# SevenSegment.net
KiCad netlist of a schematic drawn in EAGLE
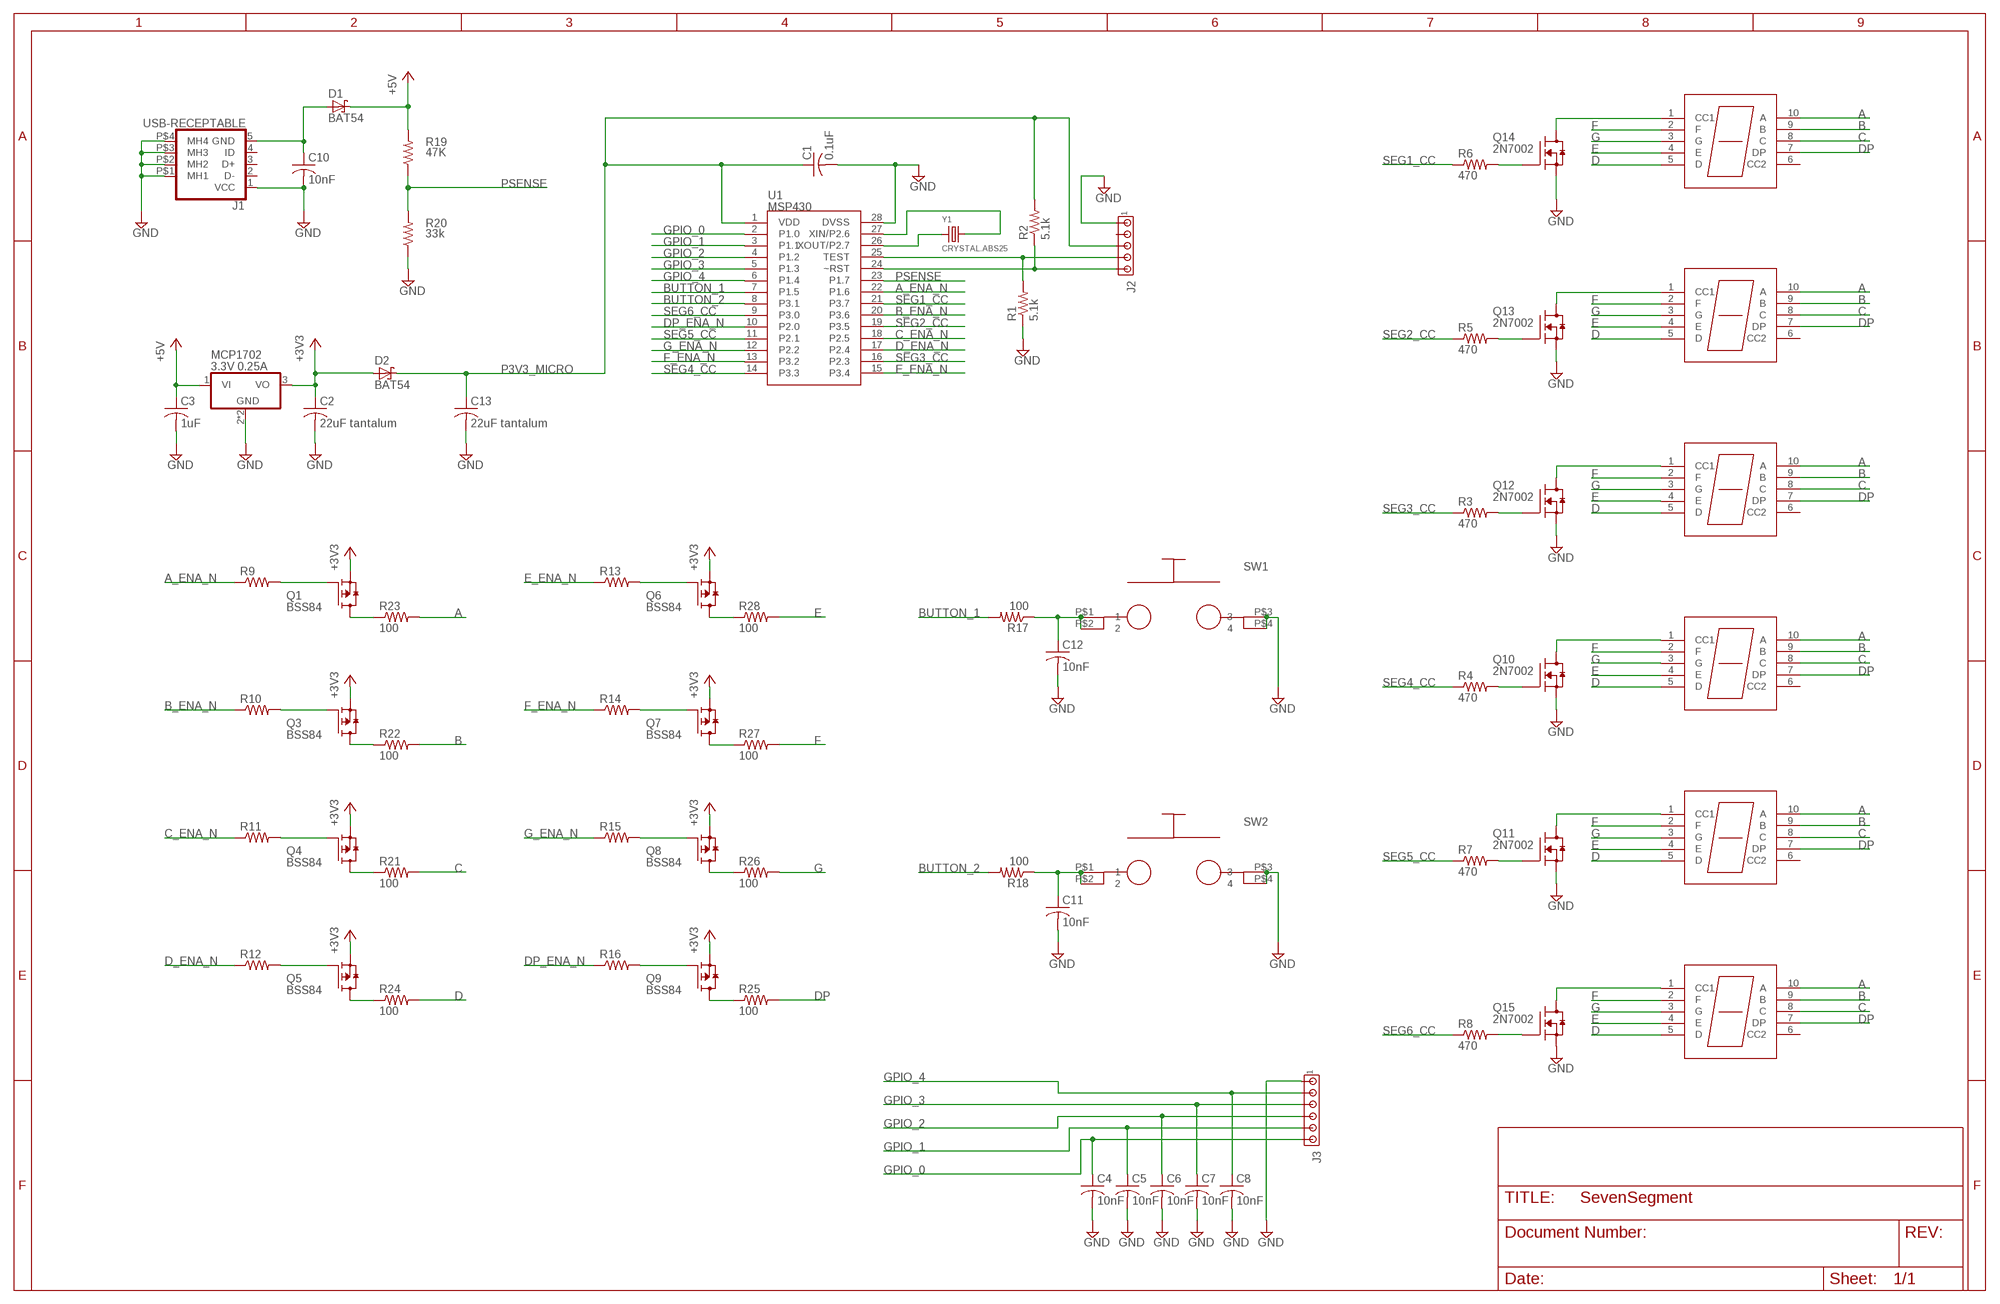
[diagram p0: schematic, sheet 1]

(export (version "E")
  (design (tool "Eeschema 10.0.6"))
  (components
    (comp (ref "C1")
      (value "0.1uF")
      (footprint "eagle-import:C0805")
      (libsource (lib "eagle-import") (part "C-USC0805"))
    )
    (comp (ref "C2")
      (value "22uF tantalum")
      (footprint "eagle-import:C3216")
      (libsource (lib "eagle-import") (part "C-USC3216"))
    )
    (comp (ref "C3")
      (value "1uF")
      (footprint "eagle-import:C0603")
      (libsource (lib "eagle-import") (part "C-USC0603"))
    )
    (comp (ref "C4")
      (value "10nF")
      (footprint "eagle-import:C0603")
      (libsource (lib "eagle-import") (part "C-USC0603"))
    )
    (comp (ref "C5")
      (value "10nF")
      (footprint "eagle-import:C0603")
      (libsource (lib "eagle-import") (part "C-USC0603"))
    )
    (comp (ref "C6")
      (value "10nF")
      (footprint "eagle-import:C0603")
      (libsource (lib "eagle-import") (part "C-USC0603"))
    )
    (comp (ref "C7")
      (value "10nF")
      (footprint "eagle-import:C0603")
      (libsource (lib "eagle-import") (part "C-USC0603"))
    )
    (comp (ref "C8")
      (value "10nF")
      (footprint "eagle-import:C0603")
      (libsource (lib "eagle-import") (part "C-USC0603"))
    )
    (comp (ref "C10")
      (value "10nF")
      (footprint "eagle-import:C0603")
      (libsource (lib "eagle-import") (part "C-USC0603"))
    )
    (comp (ref "C11")
      (value "10nF")
      (footprint "eagle-import:C0603")
      (libsource (lib "eagle-import") (part "C-USC0603"))
    )
    (comp (ref "C12")
      (value "10nF")
      (footprint "eagle-import:C0603")
      (libsource (lib "eagle-import") (part "C-USC0603"))
    )
    (comp (ref "C13")
      (value "22uF tantalum")
      (footprint "eagle-import:C3216")
      (libsource (lib "eagle-import") (part "C-USC3216"))
    )
    (comp (ref "D1")
      (value "BAT54")
      (footprint "eagle-import:SOT23")
      (libsource (lib "eagle-import") (part "BAT54"))
    )
    (comp (ref "D2")
      (value "BAT54")
      (footprint "eagle-import:SOT23")
      (libsource (lib "eagle-import") (part "BAT54"))
    )
    (comp (ref "DP1")
      (value "SEVENSEGMENT")
      (footprint "eagle-import:LA-401")
      (libsource (lib "eagle-import") (part "SEVENSEGMENT"))
    )
    (comp (ref "DP2")
      (value "SEVENSEGMENT")
      (footprint "eagle-import:LA-401")
      (libsource (lib "eagle-import") (part "SEVENSEGMENT"))
    )
    (comp (ref "DP3")
      (value "SEVENSEGMENT")
      (footprint "eagle-import:LA-401")
      (libsource (lib "eagle-import") (part "SEVENSEGMENT"))
    )
    (comp (ref "DP4")
      (value "SEVENSEGMENT")
      (footprint "eagle-import:LA-401")
      (libsource (lib "eagle-import") (part "SEVENSEGMENT"))
    )
    (comp (ref "DP5")
      (value "SEVENSEGMENT")
      (footprint "eagle-import:LA-401")
      (libsource (lib "eagle-import") (part "SEVENSEGMENT"))
    )
    (comp (ref "DP6")
      (value "SEVENSEGMENT")
      (footprint "eagle-import:LA-401")
      (libsource (lib "eagle-import") (part "SEVENSEGMENT"))
    )
    (comp (ref "J1")
      (value "USB-RECEPTABLE")
      (footprint "eagle-import:FCI-10103594-0001LF")
      (libsource (lib "eagle-import") (part "USB-RECEPTABLE"))
    )
    (comp (ref "J2")
      (value "MTA05-100")
      (footprint "eagle-import:10X05MTA")
      (libsource (lib "eagle-import") (part "MTA05-100"))
    )
    (comp (ref "J3")
      (value "MTA06-100")
      (footprint "eagle-import:10X06MTA")
      (libsource (lib "eagle-import") (part "MTA06-100"))
    )
    (comp (ref "Q1")
      (value "BSS84")
      (footprint "eagle-import:SOT-23")
      (libsource (lib "eagle-import") (part "BSS84"))
    )
    (comp (ref "Q3")
      (value "BSS84")
      (footprint "eagle-import:SOT-23")
      (libsource (lib "eagle-import") (part "BSS84"))
    )
    (comp (ref "Q4")
      (value "BSS84")
      (footprint "eagle-import:SOT-23")
      (libsource (lib "eagle-import") (part "BSS84"))
    )
    (comp (ref "Q5")
      (value "BSS84")
      (footprint "eagle-import:SOT-23")
      (libsource (lib "eagle-import") (part "BSS84"))
    )
    (comp (ref "Q6")
      (value "BSS84")
      (footprint "eagle-import:SOT-23")
      (libsource (lib "eagle-import") (part "BSS84"))
    )
    (comp (ref "Q7")
      (value "BSS84")
      (footprint "eagle-import:SOT-23")
      (libsource (lib "eagle-import") (part "BSS84"))
    )
    (comp (ref "Q8")
      (value "BSS84")
      (footprint "eagle-import:SOT-23")
      (libsource (lib "eagle-import") (part "BSS84"))
    )
    (comp (ref "Q9")
      (value "BSS84")
      (footprint "eagle-import:SOT-23")
      (libsource (lib "eagle-import") (part "BSS84"))
    )
    (comp (ref "Q10")
      (value "2N7002")
      (footprint "eagle-import:SOT-23")
      (libsource (lib "eagle-import") (part "2N7002"))
    )
    (comp (ref "Q11")
      (value "2N7002")
      (footprint "eagle-import:SOT-23")
      (libsource (lib "eagle-import") (part "2N7002"))
    )
    (comp (ref "Q12")
      (value "2N7002")
      (footprint "eagle-import:SOT-23")
      (libsource (lib "eagle-import") (part "2N7002"))
    )
    (comp (ref "Q13")
      (value "2N7002")
      (footprint "eagle-import:SOT-23")
      (libsource (lib "eagle-import") (part "2N7002"))
    )
    (comp (ref "Q14")
      (value "2N7002")
      (footprint "eagle-import:SOT-23")
      (libsource (lib "eagle-import") (part "2N7002"))
    )
    (comp (ref "Q15")
      (value "2N7002")
      (footprint "eagle-import:SOT-23")
      (libsource (lib "eagle-import") (part "2N7002"))
    )
    (comp (ref "R1")
      (value "5.1k")
      (footprint "eagle-import:R0603")
      (libsource (lib "eagle-import") (part "R-US_R0603"))
    )
    (comp (ref "R2")
      (value "5.1k")
      (footprint "eagle-import:R0603")
      (libsource (lib "eagle-import") (part "R-US_R0603"))
    )
    (comp (ref "R3")
      (value "470")
      (footprint "eagle-import:R0603")
      (libsource (lib "eagle-import") (part "R-US_R0603"))
    )
    (comp (ref "R4")
      (value "470")
      (footprint "eagle-import:R0603")
      (libsource (lib "eagle-import") (part "R-US_R0603"))
    )
    (comp (ref "R5")
      (value "470")
      (footprint "eagle-import:R0603")
      (libsource (lib "eagle-import") (part "R-US_R0603"))
    )
    (comp (ref "R6")
      (value "470")
      (footprint "eagle-import:R0603")
      (libsource (lib "eagle-import") (part "R-US_R0603"))
    )
    (comp (ref "R7")
      (value "470")
      (footprint "eagle-import:R0603")
      (libsource (lib "eagle-import") (part "R-US_R0603"))
    )
    (comp (ref "R8")
      (value "470")
      (footprint "eagle-import:R0603")
      (libsource (lib "eagle-import") (part "R-US_R0603"))
    )
    (comp (ref "R9")
      (value "R-US_R0603")
      (footprint "eagle-import:R0603")
      (libsource (lib "eagle-import") (part "R-US_R0603"))
    )
    (comp (ref "R10")
      (value "R-US_R0603")
      (footprint "eagle-import:R0603")
      (libsource (lib "eagle-import") (part "R-US_R0603"))
    )
    (comp (ref "R11")
      (value "R-US_R0603")
      (footprint "eagle-import:R0603")
      (libsource (lib "eagle-import") (part "R-US_R0603"))
    )
    (comp (ref "R12")
      (value "R-US_R0603")
      (footprint "eagle-import:R0603")
      (libsource (lib "eagle-import") (part "R-US_R0603"))
    )
    (comp (ref "R13")
      (value "R-US_R0603")
      (footprint "eagle-import:R0603")
      (libsource (lib "eagle-import") (part "R-US_R0603"))
    )
    (comp (ref "R14")
      (value "R-US_R0603")
      (footprint "eagle-import:R0603")
      (libsource (lib "eagle-import") (part "R-US_R0603"))
    )
    (comp (ref "R15")
      (value "R-US_R0603")
      (footprint "eagle-import:R0603")
      (libsource (lib "eagle-import") (part "R-US_R0603"))
    )
    (comp (ref "R16")
      (value "R-US_R0603")
      (footprint "eagle-import:R0603")
      (libsource (lib "eagle-import") (part "R-US_R0603"))
    )
    (comp (ref "R17")
      (value "100")
      (footprint "eagle-import:R0603")
      (libsource (lib "eagle-import") (part "R-US_R0603"))
    )
    (comp (ref "R18")
      (value "100")
      (footprint "eagle-import:R0603")
      (libsource (lib "eagle-import") (part "R-US_R0603"))
    )
    (comp (ref "R19")
      (value "47K")
      (footprint "eagle-import:R0603")
      (libsource (lib "eagle-import") (part "R-US_R0603"))
    )
    (comp (ref "R20")
      (value "33k")
      (footprint "eagle-import:R0603")
      (libsource (lib "eagle-import") (part "R-US_R0603"))
    )
    (comp (ref "R21")
      (value "100")
      (footprint "eagle-import:R0603")
      (libsource (lib "eagle-import") (part "R-US_R0603"))
    )
    (comp (ref "R22")
      (value "100")
      (footprint "eagle-import:R0603")
      (libsource (lib "eagle-import") (part "R-US_R0603"))
    )
    (comp (ref "R23")
      (value "100")
      (footprint "eagle-import:R0603")
      (libsource (lib "eagle-import") (part "R-US_R0603"))
    )
    (comp (ref "R24")
      (value "100")
      (footprint "eagle-import:R0603")
      (libsource (lib "eagle-import") (part "R-US_R0603"))
    )
    (comp (ref "R25")
      (value "100")
      (footprint "eagle-import:R0603")
      (libsource (lib "eagle-import") (part "R-US_R0603"))
    )
    (comp (ref "R26")
      (value "100")
      (footprint "eagle-import:R0603")
      (libsource (lib "eagle-import") (part "R-US_R0603"))
    )
    (comp (ref "R27")
      (value "100")
      (footprint "eagle-import:R0603")
      (libsource (lib "eagle-import") (part "R-US_R0603"))
    )
    (comp (ref "R28")
      (value "100")
      (footprint "eagle-import:R0603")
      (libsource (lib "eagle-import") (part "R-US_R0603"))
    )
    (comp (ref "SW1")
      (value "BUTTON")
      (footprint "eagle-import:TL6100CF300QP")
      (libsource (lib "eagle-import") (part "BUTTON"))
    )
    (comp (ref "SW2")
      (value "BUTTON")
      (footprint "eagle-import:TL6100CF300QP")
      (libsource (lib "eagle-import") (part "BUTTON"))
    )
    (comp (ref "U1")
      (value "MSP430")
      (footprint "eagle-import:TSSOP28")
      (libsource (lib "eagle-import") (part "MICRO"))
    )
    (comp (ref "U12")
      (value "VOLTAGEREG")
      (footprint "eagle-import:SOT223")
      (libsource (lib "eagle-import") (part "VOLTAGEREG"))
    )
    (comp (ref "Y1")
      (value "CRYSTAL.ABS25")
      (footprint "eagle-import:ABS25")
      (libsource (lib "eagle-import") (part "CRYSTAL.ABS25"))
    )
  )
  (nets
    (net (code "1") (name "+3V3") (class "Default")
      (node (ref "C2") (pin "1") (pinfunction "1_1") (pintype "passive"))
      (node (ref "D2") (pin "1") (pinfunction "A_1") (pintype "passive"))
      (node (ref "Q1") (pin "2") (pinfunction "S_2") (pintype "passive"))
      (node (ref "Q3") (pin "2") (pinfunction "S_2") (pintype "passive"))
      (node (ref "Q4") (pin "2") (pinfunction "S_2") (pintype "passive"))
      (node (ref "Q5") (pin "2") (pinfunction "S_2") (pintype "passive"))
      (node (ref "Q6") (pin "2") (pinfunction "S_2") (pintype "passive"))
      (node (ref "Q7") (pin "2") (pinfunction "S_2") (pintype "passive"))
      (node (ref "Q8") (pin "2") (pinfunction "S_2") (pintype "passive"))
      (node (ref "Q9") (pin "2") (pinfunction "S_2") (pintype "passive"))
      (node (ref "U12") (pin "3") (pinfunction "VO_3") (pintype "passive"))
    )
    (net (code "2") (name "+5V") (class "Default")
      (node (ref "C3") (pin "1") (pinfunction "1_1") (pintype "passive"))
      (node (ref "D1") (pin "3") (pinfunction "C_3") (pintype "passive"))
      (node (ref "R19") (pin "2") (pinfunction "2_2") (pintype "passive"))
      (node (ref "U12") (pin "1") (pinfunction "VI_1") (pintype "input"))
    )
    (net (code "3") (name "/A") (class "Default")
      (node (ref "DP1") (pin "10") (pinfunction "A_10") (pintype "passive"))
      (node (ref "DP2") (pin "10") (pinfunction "A_10") (pintype "passive"))
      (node (ref "DP3") (pin "10") (pinfunction "A_10") (pintype "passive"))
      (node (ref "DP4") (pin "10") (pinfunction "A_10") (pintype "passive"))
      (node (ref "DP5") (pin "10") (pinfunction "A_10") (pintype "passive"))
      (node (ref "DP6") (pin "10") (pinfunction "A_10") (pintype "passive"))
      (node (ref "R23") (pin "2") (pinfunction "2_2") (pintype "passive"))
    )
    (net (code "4") (name "/A_ENA_N") (class "Default")
      (node (ref "R9") (pin "1") (pinfunction "1_1") (pintype "passive"))
      (node (ref "U1") (pin "22") (pinfunction "P1.6_22") (pintype "bidirectional"))
    )
    (net (code "5") (name "/B") (class "Default")
      (node (ref "DP1") (pin "9") (pinfunction "B_9") (pintype "passive"))
      (node (ref "DP2") (pin "9") (pinfunction "B_9") (pintype "passive"))
      (node (ref "DP3") (pin "9") (pinfunction "B_9") (pintype "passive"))
      (node (ref "DP4") (pin "9") (pinfunction "B_9") (pintype "passive"))
      (node (ref "DP5") (pin "9") (pinfunction "B_9") (pintype "passive"))
      (node (ref "DP6") (pin "9") (pinfunction "B_9") (pintype "passive"))
      (node (ref "R22") (pin "2") (pinfunction "2_2") (pintype "passive"))
    )
    (net (code "6") (name "/BUTTON_1") (class "Default")
      (node (ref "R17") (pin "2") (pinfunction "2_2") (pintype "passive"))
      (node (ref "U1") (pin "7") (pinfunction "P1.5_7") (pintype "bidirectional"))
    )
    (net (code "7") (name "/BUTTON_2") (class "Default")
      (node (ref "R18") (pin "2") (pinfunction "2_2") (pintype "passive"))
      (node (ref "U1") (pin "8") (pinfunction "P3.1_8") (pintype "bidirectional"))
    )
    (net (code "8") (name "/B_ENA_N") (class "Default")
      (node (ref "R10") (pin "1") (pinfunction "1_1") (pintype "passive"))
      (node (ref "U1") (pin "20") (pinfunction "P3.6_20") (pintype "bidirectional"))
    )
    (net (code "9") (name "/C") (class "Default")
      (node (ref "DP1") (pin "8") (pinfunction "C_8") (pintype "passive"))
      (node (ref "DP2") (pin "8") (pinfunction "C_8") (pintype "passive"))
      (node (ref "DP3") (pin "8") (pinfunction "C_8") (pintype "passive"))
      (node (ref "DP4") (pin "8") (pinfunction "C_8") (pintype "passive"))
      (node (ref "DP5") (pin "8") (pinfunction "C_8") (pintype "passive"))
      (node (ref "DP6") (pin "8") (pinfunction "C_8") (pintype "passive"))
      (node (ref "R21") (pin "2") (pinfunction "2_2") (pintype "passive"))
    )
    (net (code "10") (name "/C_ENA_N") (class "Default")
      (node (ref "R11") (pin "1") (pinfunction "1_1") (pintype "passive"))
      (node (ref "U1") (pin "18") (pinfunction "P2.5_18") (pintype "bidirectional"))
    )
    (net (code "11") (name "/D") (class "Default")
      (node (ref "DP1") (pin "5") (pinfunction "D_5") (pintype "passive"))
      (node (ref "DP2") (pin "5") (pinfunction "D_5") (pintype "passive"))
      (node (ref "DP3") (pin "5") (pinfunction "D_5") (pintype "passive"))
      (node (ref "DP4") (pin "5") (pinfunction "D_5") (pintype "passive"))
      (node (ref "DP5") (pin "5") (pinfunction "D_5") (pintype "passive"))
      (node (ref "DP6") (pin "5") (pinfunction "D_5") (pintype "passive"))
      (node (ref "R24") (pin "2") (pinfunction "2_2") (pintype "passive"))
    )
    (net (code "12") (name "/DP") (class "Default")
      (node (ref "DP1") (pin "7") (pinfunction "DP_7") (pintype "passive"))
      (node (ref "DP2") (pin "7") (pinfunction "DP_7") (pintype "passive"))
      (node (ref "DP3") (pin "7") (pinfunction "DP_7") (pintype "passive"))
      (node (ref "DP4") (pin "7") (pinfunction "DP_7") (pintype "passive"))
      (node (ref "DP5") (pin "7") (pinfunction "DP_7") (pintype "passive"))
      (node (ref "DP6") (pin "7") (pinfunction "DP_7") (pintype "passive"))
      (node (ref "R25") (pin "2") (pinfunction "2_2") (pintype "passive"))
    )
    (net (code "13") (name "/DP_ENA_N") (class "Default")
      (node (ref "R16") (pin "1") (pinfunction "1_1") (pintype "passive"))
      (node (ref "U1") (pin "10") (pinfunction "P2.0_10") (pintype "bidirectional"))
    )
    (net (code "14") (name "/D_ENA_N") (class "Default")
      (node (ref "R12") (pin "1") (pinfunction "1_1") (pintype "passive"))
      (node (ref "U1") (pin "17") (pinfunction "P2.4_17") (pintype "bidirectional"))
    )
    (net (code "15") (name "/E") (class "Default")
      (node (ref "DP1") (pin "4") (pinfunction "E_4") (pintype "passive"))
      (node (ref "DP2") (pin "4") (pinfunction "E_4") (pintype "passive"))
      (node (ref "DP3") (pin "4") (pinfunction "E_4") (pintype "passive"))
      (node (ref "DP4") (pin "4") (pinfunction "E_4") (pintype "passive"))
      (node (ref "DP5") (pin "4") (pinfunction "E_4") (pintype "passive"))
      (node (ref "DP6") (pin "4") (pinfunction "E_4") (pintype "passive"))
      (node (ref "R28") (pin "2") (pinfunction "2_2") (pintype "passive"))
    )
    (net (code "16") (name "/E_ENA_N") (class "Default")
      (node (ref "R13") (pin "1") (pinfunction "1_1") (pintype "passive"))
      (node (ref "U1") (pin "15") (pinfunction "P3.4_15") (pintype "bidirectional"))
    )
    (net (code "17") (name "/F") (class "Default")
      (node (ref "DP1") (pin "2") (pinfunction "F_2") (pintype "passive"))
      (node (ref "DP2") (pin "2") (pinfunction "F_2") (pintype "passive"))
      (node (ref "DP3") (pin "2") (pinfunction "F_2") (pintype "passive"))
      (node (ref "DP4") (pin "2") (pinfunction "F_2") (pintype "passive"))
      (node (ref "DP5") (pin "2") (pinfunction "F_2") (pintype "passive"))
      (node (ref "DP6") (pin "2") (pinfunction "F_2") (pintype "passive"))
      (node (ref "R27") (pin "2") (pinfunction "2_2") (pintype "passive"))
    )
    (net (code "18") (name "/F_ENA_N") (class "Default")
      (node (ref "R14") (pin "1") (pinfunction "1_1") (pintype "passive"))
      (node (ref "U1") (pin "13") (pinfunction "P3.2_13") (pintype "bidirectional"))
    )
    (net (code "19") (name "/G") (class "Default")
      (node (ref "DP1") (pin "3") (pinfunction "G_3") (pintype "passive"))
      (node (ref "DP2") (pin "3") (pinfunction "G_3") (pintype "passive"))
      (node (ref "DP3") (pin "3") (pinfunction "G_3") (pintype "passive"))
      (node (ref "DP4") (pin "3") (pinfunction "G_3") (pintype "passive"))
      (node (ref "DP5") (pin "3") (pinfunction "G_3") (pintype "passive"))
      (node (ref "DP6") (pin "3") (pinfunction "G_3") (pintype "passive"))
      (node (ref "R26") (pin "2") (pinfunction "2_2") (pintype "passive"))
    )
    (net (code "20") (name "/GPIO_0") (class "Default")
      (node (ref "C4") (pin "1") (pinfunction "1_1") (pintype "passive"))
      (node (ref "J3") (pin "6") (pinfunction "6_6") (pintype "passive"))
      (node (ref "U1") (pin "2") (pinfunction "P1.0_2") (pintype "bidirectional"))
    )
    (net (code "21") (name "/GPIO_1") (class "Default")
      (node (ref "C5") (pin "1") (pinfunction "1_1") (pintype "passive"))
      (node (ref "J3") (pin "5") (pinfunction "5_5") (pintype "passive"))
      (node (ref "U1") (pin "3") (pinfunction "P1.1_3") (pintype "bidirectional"))
    )
    (net (code "22") (name "/GPIO_2") (class "Default")
      (node (ref "C6") (pin "1") (pinfunction "1_1") (pintype "passive"))
      (node (ref "J3") (pin "4") (pinfunction "4_4") (pintype "passive"))
      (node (ref "U1") (pin "4") (pinfunction "P1.2_4") (pintype "bidirectional"))
    )
    (net (code "23") (name "/GPIO_3") (class "Default")
      (node (ref "C7") (pin "1") (pinfunction "1_1") (pintype "passive"))
      (node (ref "J3") (pin "3") (pinfunction "3_3") (pintype "passive"))
      (node (ref "U1") (pin "5") (pinfunction "P1.3_5") (pintype "bidirectional"))
    )
    (net (code "24") (name "/GPIO_4") (class "Default")
      (node (ref "C8") (pin "1") (pinfunction "1_1") (pintype "passive"))
      (node (ref "J3") (pin "2") (pinfunction "2_2") (pintype "passive"))
      (node (ref "U1") (pin "6") (pinfunction "P1.4_6") (pintype "bidirectional"))
    )
    (net (code "25") (name "/G_ENA_N") (class "Default")
      (node (ref "R15") (pin "1") (pinfunction "1_1") (pintype "passive"))
      (node (ref "U1") (pin "12") (pinfunction "P2.2_12") (pintype "bidirectional"))
    )
    (net (code "26") (name "/P3V3_MICRO") (class "Default")
      (node (ref "C1") (pin "1") (pinfunction "1_1") (pintype "passive"))
      (node (ref "C13") (pin "1") (pinfunction "1_1") (pintype "passive"))
      (node (ref "D2") (pin "3") (pinfunction "C_3") (pintype "passive"))
      (node (ref "J2") (pin "3") (pinfunction "3_3") (pintype "passive"))
      (node (ref "R2") (pin "2") (pinfunction "2_2") (pintype "passive"))
      (node (ref "U1") (pin "1") (pinfunction "VDD_1") (pintype "power_in"))
    )
    (net (code "27") (name "/PSENSE") (class "Default")
      (node (ref "R19") (pin "1") (pinfunction "1_1") (pintype "passive"))
      (node (ref "R20") (pin "2") (pinfunction "2_2") (pintype "passive"))
      (node (ref "U1") (pin "23") (pinfunction "P1.7_23") (pintype "bidirectional"))
    )
    (net (code "28") (name "/SEG1_CC") (class "Default")
      (node (ref "R6") (pin "1") (pinfunction "1_1") (pintype "passive"))
      (node (ref "U1") (pin "21") (pinfunction "P3.7_21") (pintype "bidirectional"))
    )
    (net (code "29") (name "/SEG2_CC") (class "Default")
      (node (ref "R5") (pin "1") (pinfunction "1_1") (pintype "passive"))
      (node (ref "U1") (pin "19") (pinfunction "P3.5_19") (pintype "bidirectional"))
    )
    (net (code "30") (name "/SEG3_CC") (class "Default")
      (node (ref "R3") (pin "1") (pinfunction "1_1") (pintype "passive"))
      (node (ref "U1") (pin "16") (pinfunction "P2.3_16") (pintype "bidirectional"))
    )
    (net (code "31") (name "/SEG4_CC") (class "Default")
      (node (ref "R4") (pin "1") (pinfunction "1_1") (pintype "passive"))
      (node (ref "U1") (pin "14") (pinfunction "P3.3_14") (pintype "bidirectional"))
    )
    (net (code "32") (name "/SEG5_CC") (class "Default")
      (node (ref "R7") (pin "1") (pinfunction "1_1") (pintype "passive"))
      (node (ref "U1") (pin "11") (pinfunction "P2.1_11") (pintype "bidirectional"))
    )
    (net (code "33") (name "/SEG6_CC") (class "Default")
      (node (ref "R8") (pin "1") (pinfunction "1_1") (pintype "passive"))
      (node (ref "U1") (pin "9") (pinfunction "P3.0_9") (pintype "bidirectional"))
    )
    (net (code "34") (name "GND") (class "Default")
      (node (ref "C1") (pin "2") (pinfunction "2_2") (pintype "passive"))
      (node (ref "C10") (pin "2") (pinfunction "2_2") (pintype "passive"))
      (node (ref "C11") (pin "2") (pinfunction "2_2") (pintype "passive"))
      (node (ref "C12") (pin "2") (pinfunction "2_2") (pintype "passive"))
      (node (ref "C13") (pin "2") (pinfunction "2_2") (pintype "passive"))
      (node (ref "C2") (pin "2") (pinfunction "2_2") (pintype "passive"))
      (node (ref "C3") (pin "2") (pinfunction "2_2") (pintype "passive"))
      (node (ref "C4") (pin "2") (pinfunction "2_2") (pintype "passive"))
      (node (ref "C5") (pin "2") (pinfunction "2_2") (pintype "passive"))
      (node (ref "C6") (pin "2") (pinfunction "2_2") (pintype "passive"))
      (node (ref "C7") (pin "2") (pinfunction "2_2") (pintype "passive"))
      (node (ref "C8") (pin "2") (pinfunction "2_2") (pintype "passive"))
      (node (ref "J1") (pin "1") (pinfunction "VCC_1") (pintype "bidirectional"))
      (node (ref "J1") (pin "P$1") (pinfunction "MH1_P$1") (pintype "bidirectional"))
      (node (ref "J1") (pin "P$2") (pinfunction "MH2_P$2") (pintype "bidirectional"))
      (node (ref "J1") (pin "P$3") (pinfunction "MH3_P$3") (pintype "bidirectional"))
      (node (ref "J1") (pin "P$4") (pinfunction "MH4_P$4") (pintype "bidirectional"))
      (node (ref "J2") (pin "1") (pinfunction "1_1") (pintype "passive"))
      (node (ref "J3") (pin "1") (pinfunction "1_1") (pintype "passive"))
      (node (ref "Q10") (pin "2") (pinfunction "S_2") (pintype "passive"))
      (node (ref "Q11") (pin "2") (pinfunction "S_2") (pintype "passive"))
      (node (ref "Q12") (pin "2") (pinfunction "S_2") (pintype "passive"))
      (node (ref "Q13") (pin "2") (pinfunction "S_2") (pintype "passive"))
      (node (ref "Q14") (pin "2") (pinfunction "S_2") (pintype "passive"))
      (node (ref "Q15") (pin "2") (pinfunction "S_2") (pintype "passive"))
      (node (ref "R1") (pin "1") (pinfunction "1_1") (pintype "passive"))
      (node (ref "R20") (pin "1") (pinfunction "1_1") (pintype "passive"))
      (node (ref "SW1") (pin "P$3") (pinfunction "3_P$3") (pintype "passive"))
      (node (ref "SW1") (pin "P$4") (pinfunction "4_P$4") (pintype "passive"))
      (node (ref "SW2") (pin "P$3") (pinfunction "3_P$3") (pintype "passive"))
      (node (ref "SW2") (pin "P$4") (pinfunction "4_P$4") (pintype "passive"))
      (node (ref "U1") (pin "28") (pinfunction "DVSS_28") (pintype "power_in"))
      (node (ref "U12") (pin "2") (pinfunction "GND_2") (pintype "passive"))
      (node (ref "U12") (pin "4") (pinfunction "GND_4") (pintype "passive"))
    )
    (net (code "35") (name "Net-(D1-A)") (class "Default")
      (node (ref "C10") (pin "1") (pinfunction "1_1") (pintype "passive"))
      (node (ref "D1") (pin "1") (pinfunction "A_1") (pintype "passive"))
      (node (ref "J1") (pin "5") (pinfunction "GND_5") (pintype "bidirectional"))
    )
    (net (code "36") (name "Net-(DP1-CC1)") (class "Default")
      (node (ref "DP1") (pin "1") (pinfunction "CC1_1") (pintype "passive"))
      (node (ref "Q14") (pin "3") (pinfunction "D_3") (pintype "passive"))
    )
    (net (code "37") (name "Net-(DP2-CC1)") (class "Default")
      (node (ref "DP2") (pin "1") (pinfunction "CC1_1") (pintype "passive"))
      (node (ref "Q13") (pin "3") (pinfunction "D_3") (pintype "passive"))
    )
    (net (code "38") (name "Net-(DP3-CC1)") (class "Default")
      (node (ref "DP3") (pin "1") (pinfunction "CC1_1") (pintype "passive"))
      (node (ref "Q12") (pin "3") (pinfunction "D_3") (pintype "passive"))
    )
    (net (code "39") (name "Net-(DP4-CC1)") (class "Default")
      (node (ref "DP4") (pin "1") (pinfunction "CC1_1") (pintype "passive"))
      (node (ref "Q10") (pin "3") (pinfunction "D_3") (pintype "passive"))
    )
    (net (code "40") (name "Net-(DP5-CC1)") (class "Default")
      (node (ref "DP5") (pin "1") (pinfunction "CC1_1") (pintype "passive"))
      (node (ref "Q11") (pin "3") (pinfunction "D_3") (pintype "passive"))
    )
    (net (code "41") (name "Net-(DP6-CC1)") (class "Default")
      (node (ref "DP6") (pin "1") (pinfunction "CC1_1") (pintype "passive"))
      (node (ref "Q15") (pin "3") (pinfunction "D_3") (pintype "passive"))
    )
    (net (code "42") (name "Net-(Q1-D)") (class "Default")
      (node (ref "Q1") (pin "3") (pinfunction "D_3") (pintype "passive"))
      (node (ref "R23") (pin "1") (pinfunction "1_1") (pintype "passive"))
    )
    (net (code "43") (name "Net-(Q1-G)") (class "Default")
      (node (ref "Q1") (pin "1") (pinfunction "G_1") (pintype "passive"))
      (node (ref "R9") (pin "2") (pinfunction "2_2") (pintype "passive"))
    )
    (net (code "44") (name "Net-(Q3-D)") (class "Default")
      (node (ref "Q3") (pin "3") (pinfunction "D_3") (pintype "passive"))
      (node (ref "R22") (pin "1") (pinfunction "1_1") (pintype "passive"))
    )
    (net (code "45") (name "Net-(Q3-G)") (class "Default")
      (node (ref "Q3") (pin "1") (pinfunction "G_1") (pintype "passive"))
      (node (ref "R10") (pin "2") (pinfunction "2_2") (pintype "passive"))
    )
    (net (code "46") (name "Net-(Q4-D)") (class "Default")
      (node (ref "Q4") (pin "3") (pinfunction "D_3") (pintype "passive"))
      (node (ref "R21") (pin "1") (pinfunction "1_1") (pintype "passive"))
    )
    (net (code "47") (name "Net-(Q4-G)") (class "Default")
      (node (ref "Q4") (pin "1") (pinfunction "G_1") (pintype "passive"))
      (node (ref "R11") (pin "2") (pinfunction "2_2") (pintype "passive"))
    )
    (net (code "48") (name "Net-(Q5-D)") (class "Default")
      (node (ref "Q5") (pin "3") (pinfunction "D_3") (pintype "passive"))
      (node (ref "R24") (pin "1") (pinfunction "1_1") (pintype "passive"))
    )
    (net (code "49") (name "Net-(Q5-G)") (class "Default")
      (node (ref "Q5") (pin "1") (pinfunction "G_1") (pintype "passive"))
      (node (ref "R12") (pin "2") (pinfunction "2_2") (pintype "passive"))
    )
    (net (code "50") (name "Net-(Q6-D)") (class "Default")
      (node (ref "Q6") (pin "3") (pinfunction "D_3") (pintype "passive"))
      (node (ref "R28") (pin "1") (pinfunction "1_1") (pintype "passive"))
    )
    (net (code "51") (name "Net-(Q6-G)") (class "Default")
      (node (ref "Q6") (pin "1") (pinfunction "G_1") (pintype "passive"))
      (node (ref "R13") (pin "2") (pinfunction "2_2") (pintype "passive"))
    )
    (net (code "52") (name "Net-(Q7-D)") (class "Default")
      (node (ref "Q7") (pin "3") (pinfunction "D_3") (pintype "passive"))
      (node (ref "R27") (pin "1") (pinfunction "1_1") (pintype "passive"))
    )
    (net (code "53") (name "Net-(Q7-G)") (class "Default")
      (node (ref "Q7") (pin "1") (pinfunction "G_1") (pintype "passive"))
      (node (ref "R14") (pin "2") (pinfunction "2_2") (pintype "passive"))
    )
    (net (code "54") (name "Net-(Q8-D)") (class "Default")
      (node (ref "Q8") (pin "3") (pinfunction "D_3") (pintype "passive"))
      (node (ref "R26") (pin "1") (pinfunction "1_1") (pintype "passive"))
    )
    (net (code "55") (name "Net-(Q8-G)") (class "Default")
      (node (ref "Q8") (pin "1") (pinfunction "G_1") (pintype "passive"))
      (node (ref "R15") (pin "2") (pinfunction "2_2") (pintype "passive"))
    )
    (net (code "56") (name "Net-(Q9-D)") (class "Default")
      (node (ref "Q9") (pin "3") (pinfunction "D_3") (pintype "passive"))
      (node (ref "R25") (pin "1") (pinfunction "1_1") (pintype "passive"))
    )
    (net (code "57") (name "Net-(Q9-G)") (class "Default")
      (node (ref "Q9") (pin "1") (pinfunction "G_1") (pintype "passive"))
      (node (ref "R16") (pin "2") (pinfunction "2_2") (pintype "passive"))
    )
    (net (code "58") (name "Net-(Q10-G)") (class "Default")
      (node (ref "Q10") (pin "1") (pinfunction "G_1") (pintype "passive"))
      (node (ref "R4") (pin "2") (pinfunction "2_2") (pintype "passive"))
    )
    (net (code "59") (name "Net-(Q11-G)") (class "Default")
      (node (ref "Q11") (pin "1") (pinfunction "G_1") (pintype "passive"))
      (node (ref "R7") (pin "2") (pinfunction "2_2") (pintype "passive"))
    )
    (net (code "60") (name "Net-(Q12-G)") (class "Default")
      (node (ref "Q12") (pin "1") (pinfunction "G_1") (pintype "passive"))
      (node (ref "R3") (pin "2") (pinfunction "2_2") (pintype "passive"))
    )
    (net (code "61") (name "Net-(Q13-G)") (class "Default")
      (node (ref "Q13") (pin "1") (pinfunction "G_1") (pintype "passive"))
      (node (ref "R5") (pin "2") (pinfunction "2_2") (pintype "passive"))
    )
    (net (code "62") (name "Net-(Q14-G)") (class "Default")
      (node (ref "Q14") (pin "1") (pinfunction "G_1") (pintype "passive"))
      (node (ref "R6") (pin "2") (pinfunction "2_2") (pintype "passive"))
    )
    (net (code "63") (name "Net-(Q15-G)") (class "Default")
      (node (ref "Q15") (pin "1") (pinfunction "G_1") (pintype "passive"))
      (node (ref "R8") (pin "2") (pinfunction "2_2") (pintype "passive"))
    )
    (net (code "64") (name "Net-(SW1-1)") (class "Default")
      (node (ref "C12") (pin "1") (pinfunction "1_1") (pintype "passive"))
      (node (ref "R17") (pin "1") (pinfunction "1_1") (pintype "passive"))
      (node (ref "SW1") (pin "P$1") (pinfunction "1_P$1") (pintype "passive"))
      (node (ref "SW1") (pin "P$2") (pinfunction "2_P$2") (pintype "passive"))
    )
    (net (code "65") (name "Net-(SW2-1)") (class "Default")
      (node (ref "C11") (pin "1") (pinfunction "1_1") (pintype "passive"))
      (node (ref "R18") (pin "1") (pinfunction "1_1") (pintype "passive"))
      (node (ref "SW2") (pin "P$1") (pinfunction "1_P$1") (pintype "passive"))
      (node (ref "SW2") (pin "P$2") (pinfunction "2_P$2") (pintype "passive"))
    )
    (net (code "66") (name "Net-(U1-TEST)") (class "Default")
      (node (ref "J2") (pin "4") (pinfunction "4_4") (pintype "passive"))
      (node (ref "R1") (pin "2") (pinfunction "2_2") (pintype "passive"))
      (node (ref "U1") (pin "25") (pinfunction "TEST_25") (pintype "bidirectional"))
    )
    (net (code "67") (name "Net-(U1-XIN{slash}P2.6)") (class "Default")
      (node (ref "U1") (pin "27") (pinfunction "XIN/P2.6_27") (pintype "bidirectional"))
      (node (ref "Y1") (pin "4") (pinfunction "2_4") (pintype "passive"))
    )
    (net (code "68") (name "Net-(U1-XOUT{slash}P2.7)") (class "Default")
      (node (ref "U1") (pin "26") (pinfunction "XOUT/P2.7_26") (pintype "bidirectional"))
      (node (ref "Y1") (pin "1") (pinfunction "1_1") (pintype "passive"))
    )
    (net (code "69") (name "Net-(U1-~{RST})") (class "Default")
      (node (ref "J2") (pin "5") (pinfunction "5_5") (pintype "passive"))
      (node (ref "R2") (pin "1") (pinfunction "1_1") (pintype "passive"))
      (node (ref "U1") (pin "24") (pinfunction "~{RST}_24") (pintype "bidirectional"))
    )
    (net (code "70") (name "unconnected-(DP1-CC2-Pad6)") (class "Default")
      (node (ref "DP1") (pin "6") (pinfunction "CC2_6") (pintype "passive"))
    )
    (net (code "71") (name "unconnected-(DP2-CC2-Pad6)") (class "Default")
      (node (ref "DP2") (pin "6") (pinfunction "CC2_6") (pintype "passive"))
    )
    (net (code "72") (name "unconnected-(DP3-CC2-Pad6)") (class "Default")
      (node (ref "DP3") (pin "6") (pinfunction "CC2_6") (pintype "passive"))
    )
    (net (code "73") (name "unconnected-(DP4-CC2-Pad6)") (class "Default")
      (node (ref "DP4") (pin "6") (pinfunction "CC2_6") (pintype "passive"))
    )
    (net (code "74") (name "unconnected-(DP5-CC2-Pad6)") (class "Default")
      (node (ref "DP5") (pin "6") (pinfunction "CC2_6") (pintype "passive"))
    )
    (net (code "75") (name "unconnected-(DP6-CC2-Pad6)") (class "Default")
      (node (ref "DP6") (pin "6") (pinfunction "CC2_6") (pintype "passive"))
    )
    (net (code "76") (name "unconnected-(J1-D+-Pad3)") (class "Default")
      (node (ref "J1") (pin "3") (pinfunction "D+_3") (pintype "bidirectional"))
    )
    (net (code "77") (name "unconnected-(J1-D--Pad2)") (class "Default")
      (node (ref "J1") (pin "2") (pinfunction "D-_2") (pintype "bidirectional"))
    )
    (net (code "78") (name "unconnected-(J1-ID-Pad4)") (class "Default")
      (node (ref "J1") (pin "4") (pinfunction "ID_4") (pintype "bidirectional"))
    )
    (net (code "79") (name "unconnected-(J2-Pad2)") (class "Default")
      (node (ref "J2") (pin "2") (pinfunction "2_2") (pintype "passive"))
    )
  )
)
